# design.net
KiCad netlist of a schematic drawn in Altium Designer
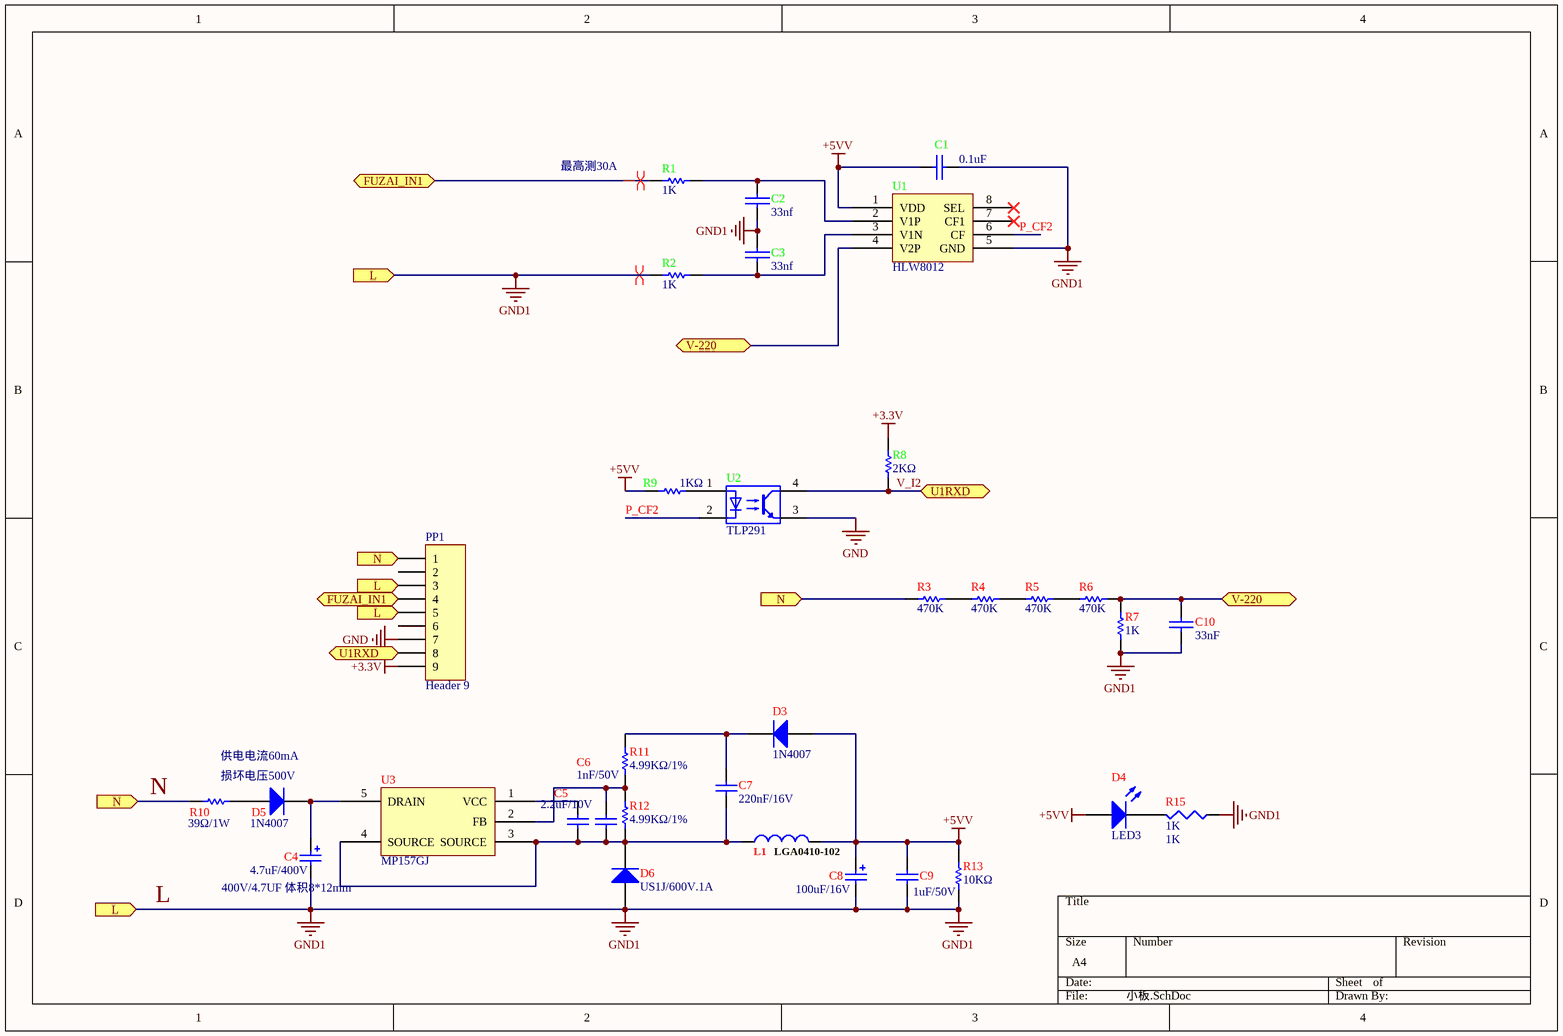
[diagram p0: 小板.SchDoc]

(export (version "E")
  (design (tool "Eeschema 10.0.6"))
  (components
    (comp (ref "C1")
      (value "0.1uF")
      (footprint "C0603")
      (description "Capacitor")
      (libsource (lib "*") (part "CAP"))
    )
    (comp (ref "C2")
      (value "33nf")
      (footprint "C0603")
      (description "Capacitor")
      (libsource (lib "*") (part "CAP"))
    )
    (comp (ref "C3")
      (value "33nf")
      (footprint "C0603")
      (description "Capacitor")
      (libsource (lib "*") (part "CAP"))
    )
    (comp (ref "C4")
      (value "400V/4.7UF 体积8*12mm")
      (footprint "4.7/400")
      (description "插件电解电容")
      (fields (field (name "ALTIUM_VALUE") "4.7uF/400V") (field (name "PUBLISHER") "Altium Limited"))
      (libsource (lib "*") (part "Cap Pol2"))
    )
    (comp (ref "C5")
      (value "2.2uF/10V")
      (footprint "C0603")
      (description "贴片电容")
      (fields (field (name "PUBLISHER") "Altium Limited"))
      (libsource (lib "*") (part "Cap"))
    )
    (comp (ref "C6")
      (value "1nF/50V")
      (footprint "C0603")
      (description "贴片电容")
      (fields (field (name "PUBLISHER") "Altium Limited"))
      (libsource (lib "*") (part "Cap"))
    )
    (comp (ref "C7")
      (value "220nF/16V")
      (footprint "C0603")
      (description "贴片电容")
      (fields (field (name "PUBLISHER") "Altium Limited"))
      (libsource (lib "*") (part "Cap"))
    )
    (comp (ref "C8")
      (value "100uF/16V")
      (footprint "RB.1/.2")
      (description "插件电解电容")
      (fields (field (name "PUBLISHER") "Altium Limited"))
      (libsource (lib "*") (part "Cap Pol2"))
    )
    (comp (ref "C9")
      (value "1uF/50V")
      (footprint "C0603")
      (description "贴片电容")
      (fields (field (name "PUBLISHER") "Altium Limited"))
      (libsource (lib "*") (part "Cap"))
    )
    (comp (ref "C10")
      (value "33nF")
      (footprint "C0603")
      (description "贴片电容")
      (libsource (lib "*") (part "贴片电容"))
    )
    (comp (ref "D3")
      (value "1N4007")
      (footprint "DO-214")
      (description "贴片二极管")
      (fields
        (field (name "MANUFACTURER") "Generic Components")
        (field (name "PUBLISHER") "Altium Hobart Technology Centre")
      )
      (libsource (lib "*") (part "二极管"))
    )
    (comp (ref "D4")
      (value "LED3")
      (footprint "L-0805")
      (description "红色贴片二极管")
      (fields (field (name "PUBLISHER") "Altium Limited"))
      (libsource (lib "Miscellaneous Devices") (part "LED3"))
    )
    (comp (ref "D5")
      (value "1N4007")
      (footprint "DO-214")
      (description "贴片二极管")
      (fields
        (field (name "MANUFACTURER") "Generic Components")
        (field (name "PUBLISHER") "Altium Hobart Technology Centre")
      )
      (libsource (lib "*") (part "二极管"))
    )
    (comp (ref "D6")
      (value "US1J/600V.1A")
      (footprint "DO-214")
      (description "贴片二极管")
      (fields
        (field (name "MANUFACTURER") "Generic Components")
        (field (name "PUBLISHER") "Altium Hobart Technology Centre")
      )
      (libsource (lib "") (part "二极管_1"))
    )
    (comp (ref "L1") (value "LGA0410-102") (footprint "L-8*10") (libsource (lib "*") (part "INDUCTOR")))
    (comp (ref "PP1")
      (value "Header 9")
      (footprint "HDR1X9")
      (description "Header, 9-Pin")
      (fields (field (name "PUBLISHER") "Altium Limited"))
      (libsource (lib "Miscellaneous Connectors") (part "Header 9"))
    )
    (comp (ref "R1")
      (value "1K")
      (footprint "3-0603")
      (description "Resistor")
      (fields (field (name "PUBLISHER") "Altium Limited"))
      (libsource (lib "*") (part "Res1"))
    )
    (comp (ref "R2")
      (value "1K")
      (footprint "3-0603")
      (description "Resistor")
      (fields (field (name "PUBLISHER") "Altium Limited"))
      (libsource (lib "*") (part "Res1"))
    )
    (comp (ref "R3")
      (value "470K")
      (footprint "3-0603")
      (description "贴片电阻")
      (fields (field (name "PUBLISHER") "Altium Limited"))
      (libsource (lib "*") (part "Res1"))
    )
    (comp (ref "R4")
      (value "470K")
      (footprint "3-0603")
      (description "贴片电阻")
      (fields (field (name "PUBLISHER") "Altium Limited"))
      (libsource (lib "*") (part "Res1"))
    )
    (comp (ref "R5")
      (value "470K")
      (footprint "3-0603")
      (description "贴片电阻")
      (fields (field (name "PUBLISHER") "Altium Limited"))
      (libsource (lib "*") (part "Res1"))
    )
    (comp (ref "R6")
      (value "470K")
      (footprint "3-0603")
      (description "贴片电阻")
      (fields (field (name "PUBLISHER") "Altium Limited"))
      (libsource (lib "*") (part "Res1"))
    )
    (comp (ref "R7")
      (value "1K")
      (footprint "3-0603")
      (description "贴片电阻")
      (fields (field (name "PUBLISHER") "Altium Limited"))
      (libsource (lib "*") (part "Res1"))
    )
    (comp (ref "R8")
      (value "2KΩ")
      (footprint "3-0603")
      (description "Resistor")
      (fields (field (name "PUBLISHER") "Altium Limited"))
      (libsource (lib "*") (part "Res1"))
    )
    (comp (ref "R9")
      (value "1KΩ")
      (footprint "3-0603")
      (description "Resistor")
      (fields (field (name "PUBLISHER") "Altium Limited"))
      (libsource (lib "*") (part "Res1"))
    )
    (comp (ref "R10")
      (value "39Ω/1W")
      (footprint "AXIAL0.6")
      (description "直插电阻")
      (fields (field (name "PUBLISHER") "Altium Limited"))
      (libsource (lib "*") (part "Res1"))
    )
    (comp (ref "R11")
      (value "4.99KΩ/1%")
      (footprint "3-0603")
      (description "贴片电阻")
      (fields (field (name "PUBLISHER") "Altium Limited"))
      (libsource (lib "*") (part "Res1"))
    )
    (comp (ref "R12")
      (value "4.99KΩ/1%")
      (footprint "3-0603")
      (description "贴片电阻")
      (fields (field (name "PUBLISHER") "Altium Limited"))
      (libsource (lib "*") (part "Res1"))
    )
    (comp (ref "R13")
      (value "10KΩ")
      (footprint "3-0603")
      (description "贴片电阻")
      (fields (field (name "PUBLISHER") "Altium Limited"))
      (libsource (lib "*") (part "Res1"))
    )
    (comp (ref "R15")
      (value "1K")
      (footprint "3-0603")
      (description "贴片电阻")
      (fields (field (name "ALTIUM_VALUE") "1K") (field (name "PUBLISHER") "Altium Limited"))
      (libsource (lib "Miscellaneous Devices") (part "Res3"))
    )
    (comp (ref "U1") (value "HLW8012") (footprint "SOP8") (libsource (lib "*") (part "HLW8012")))
    (comp (ref "U2")
      (value "TLP291")
      (footprint "PS2811-SOP4")
      (description "TLP28-2P")
      (libsource (lib "*") (part "TLP521-1"))
    )
    (comp (ref "U3")
      (value "MP157GJ")
      (footprint "SOT-23-5")
      (description "电源芯片")
      (libsource (lib "*") (part "MP150"))
    )
  )
  (nets
    (net (code "1") (name "+3.3V") (class "Default")
      (node (ref "PP1") (pin "9") (pinfunction "9_9") (pintype "passive"))
      (node (ref "R8") (pin "2") (pinfunction "2_2") (pintype "passive"))
    )
    (net (code "2") (name "+5VV") (class "Default")
      (node (ref "C1") (pin "1") (pinfunction "1_1") (pintype "passive"))
      (node (ref "C8") (pin "1") (pinfunction "1_1") (pintype "passive"))
      (node (ref "C9") (pin "1") (pinfunction "1_1") (pintype "passive"))
      (node (ref "D3") (pin "1") (pinfunction "1_1") (pintype "passive"))
      (node (ref "D4") (pin "1") (pinfunction "A_1") (pintype "passive"))
      (node (ref "L1") (pin "2") (pinfunction "2_2") (pintype "passive"))
      (node (ref "R13") (pin "2") (pinfunction "2_2") (pintype "passive"))
      (node (ref "R9") (pin "1") (pinfunction "1_1") (pintype "passive"))
      (node (ref "U1") (pin "1") (pinfunction "VDD_1") (pintype "passive"))
    )
    (net (code "3") (name "/FUZAI_IN1") (class "Default")
      (node (ref "PP1") (pin "4") (pinfunction "4_4") (pintype "passive"))
      (node (ref "R1") (pin "2") (pinfunction "2_2") (pintype "passive"))
    )
    (net (code "4") (name "/N") (class "Default")
      (node (ref "PP1") (pin "1") (pinfunction "1_1") (pintype "passive"))
      (node (ref "R10") (pin "1") (pinfunction "1_1") (pintype "passive"))
      (node (ref "R3") (pin "1") (pinfunction "1_1") (pintype "passive"))
    )
    (net (code "5") (name "/P_CF2") (class "Default")
      (node (ref "U1") (pin "6") (pinfunction "CF_6") (pintype "passive"))
      (node (ref "U2") (pin "2") (pintype "passive"))
    )
    (net (code "6") (name "/V-220") (class "Default")
      (node (ref "C10") (pin "2") (pinfunction "2_2") (pintype "passive"))
      (node (ref "R6") (pin "2") (pinfunction "2_2") (pintype "passive"))
      (node (ref "R7") (pin "2") (pinfunction "2_2") (pintype "passive"))
      (node (ref "U1") (pin "4") (pinfunction "V2P_4") (pintype "passive"))
    )
    (net (code "7") (name "/V_I2") (class "Default")
      (node (ref "PP1") (pin "8") (pinfunction "8_8") (pintype "passive"))
      (node (ref "R8") (pin "1") (pinfunction "1_1") (pintype "passive"))
      (node (ref "U2") (pin "4") (pintype "passive"))
    )
    (net (code "8") (name "GND") (class "Default")
      (node (ref "PP1") (pin "7") (pinfunction "7_7") (pintype "passive"))
      (node (ref "U2") (pin "3") (pintype "passive"))
    )
    (net (code "9") (name "GND1") (class "Default")
      (node (ref "C1") (pin "2") (pinfunction "2_2") (pintype "passive"))
      (node (ref "C10") (pin "1") (pinfunction "1_1") (pintype "passive"))
      (node (ref "C2") (pin "2") (pinfunction "2_2") (pintype "passive"))
      (node (ref "C3") (pin "1") (pinfunction "1_1") (pintype "passive"))
      (node (ref "C4") (pin "2") (pinfunction "2_2") (pintype "passive"))
      (node (ref "C8") (pin "2") (pinfunction "2_2") (pintype "passive"))
      (node (ref "C9") (pin "2") (pinfunction "2_2") (pintype "passive"))
      (node (ref "D6") (pin "1") (pinfunction "1_1") (pintype "passive"))
      (node (ref "PP1") (pin "3") (pinfunction "3_3") (pintype "passive"))
      (node (ref "PP1") (pin "5") (pinfunction "5_5") (pintype "passive"))
      (node (ref "R13") (pin "1") (pinfunction "1_1") (pintype "passive"))
      (node (ref "R15") (pin "1") (pinfunction "1_1") (pintype "passive"))
      (node (ref "R2") (pin "2") (pinfunction "2_2") (pintype "passive"))
      (node (ref "R7") (pin "1") (pinfunction "1_1") (pintype "passive"))
      (node (ref "U1") (pin "5") (pinfunction "GND_5") (pintype "passive"))
    )
    (net (code "10") (name "Net-(C5-Pad2)") (class "Default")
      (node (ref "C5") (pin "2") (pinfunction "2_2") (pintype "passive"))
      (node (ref "C6") (pin "2") (pinfunction "2_2") (pintype "passive"))
      (node (ref "C7") (pin "2") (pinfunction "2_2") (pintype "passive"))
      (node (ref "D6") (pin "2") (pinfunction "2_2") (pintype "passive"))
      (node (ref "L1") (pin "1") (pinfunction "1_1") (pintype "passive"))
      (node (ref "R12") (pin "2") (pinfunction "2_2") (pintype "passive"))
      (node (ref "U3") (pin "3") (pinfunction "SOURCE_3") (pintype "passive"))
      (node (ref "U3") (pin "4") (pinfunction "SOURCE_4") (pintype "passive"))
    )
    (net (code "11") (name "Net-(C7-Pad1)") (class "Default")
      (node (ref "C7") (pin "1") (pinfunction "1_1") (pintype "passive"))
      (node (ref "D3") (pin "2") (pinfunction "2_2") (pintype "passive"))
      (node (ref "R11") (pin "2") (pinfunction "2_2") (pintype "passive"))
    )
    (net (code "12") (name "Net-(D4-K)") (class "Default")
      (node (ref "D4") (pin "2") (pinfunction "K_2") (pintype "passive"))
      (node (ref "R15") (pin "2") (pinfunction "2_2") (pintype "passive"))
    )
    (net (code "13") (name "Net-(D5-Pad1)") (class "Default")
      (node (ref "D5") (pin "1") (pinfunction "1_1") (pintype "passive"))
      (node (ref "R10") (pin "2") (pinfunction "2_2") (pintype "passive"))
    )
    (net (code "14") (name "Net-(R3-Pad2)") (class "Default")
      (node (ref "R3") (pin "2") (pinfunction "2_2") (pintype "passive"))
      (node (ref "R4") (pin "1") (pinfunction "1_1") (pintype "passive"))
    )
    (net (code "15") (name "Net-(R4-Pad2)") (class "Default")
      (node (ref "R4") (pin "2") (pinfunction "2_2") (pintype "passive"))
      (node (ref "R5") (pin "1") (pinfunction "1_1") (pintype "passive"))
    )
    (net (code "16") (name "Net-(R5-Pad2)") (class "Default")
      (node (ref "R5") (pin "2") (pinfunction "2_2") (pintype "passive"))
      (node (ref "R6") (pin "1") (pinfunction "1_1") (pintype "passive"))
    )
    (net (code "17") (name "Net-(R9-Pad2)") (class "Default")
      (node (ref "R9") (pin "2") (pinfunction "2_2") (pintype "passive"))
      (node (ref "U2") (pin "1") (pintype "passive"))
    )
    (net (code "18") (name "Net-(U1-V1N)") (class "Default")
      (node (ref "C3") (pin "2") (pinfunction "2_2") (pintype "passive"))
      (node (ref "R2") (pin "1") (pinfunction "1_1") (pintype "passive"))
      (node (ref "U1") (pin "3") (pinfunction "V1N_3") (pintype "passive"))
    )
    (net (code "19") (name "Net-(U1-V1P)") (class "Default")
      (node (ref "C2") (pin "1") (pinfunction "1_1") (pintype "passive"))
      (node (ref "R1") (pin "1") (pinfunction "1_1") (pintype "passive"))
      (node (ref "U1") (pin "2") (pinfunction "V1P_2") (pintype "passive"))
    )
    (net (code "20") (name "Net-(U3-DRAIN)") (class "Default")
      (node (ref "C4") (pin "1") (pinfunction "1_1") (pintype "passive"))
      (node (ref "D5") (pin "2") (pinfunction "2_2") (pintype "passive"))
      (node (ref "U3") (pin "5") (pinfunction "DRAIN_5") (pintype "passive"))
    )
    (net (code "21") (name "Net-(U3-FB)") (class "Default")
      (node (ref "C6") (pin "1") (pinfunction "1_1") (pintype "passive"))
      (node (ref "R11") (pin "1") (pinfunction "1_1") (pintype "passive"))
      (node (ref "R12") (pin "1") (pinfunction "1_1") (pintype "passive"))
      (node (ref "U3") (pin "2") (pinfunction "FB_2") (pintype "passive"))
    )
    (net (code "22") (name "Net-(U3-VCC)") (class "Default")
      (node (ref "C5") (pin "1") (pinfunction "1_1") (pintype "passive"))
      (node (ref "U3") (pin "1") (pinfunction "VCC_1") (pintype "passive"))
    )
    (net (code "23") (name "unconnected-(PP1-Pad2)") (class "Default")
      (node (ref "PP1") (pin "2") (pinfunction "2_2") (pintype "passive"))
    )
    (net (code "24") (name "unconnected-(PP1-Pad6)") (class "Default")
      (node (ref "PP1") (pin "6") (pinfunction "6_6") (pintype "passive"))
    )
    (net (code "25") (name "unconnected-(U1-CF1-Pad7)") (class "Default")
      (node (ref "U1") (pin "7") (pinfunction "CF1_7") (pintype "passive+no_connect"))
    )
    (net (code "26") (name "unconnected-(U1-SEL-Pad8)") (class "Default")
      (node (ref "U1") (pin "8") (pinfunction "SEL_8") (pintype "passive+no_connect"))
    )
  )
)
